# Filter.net
KiCad netlist of a schematic drawn in EAGLE
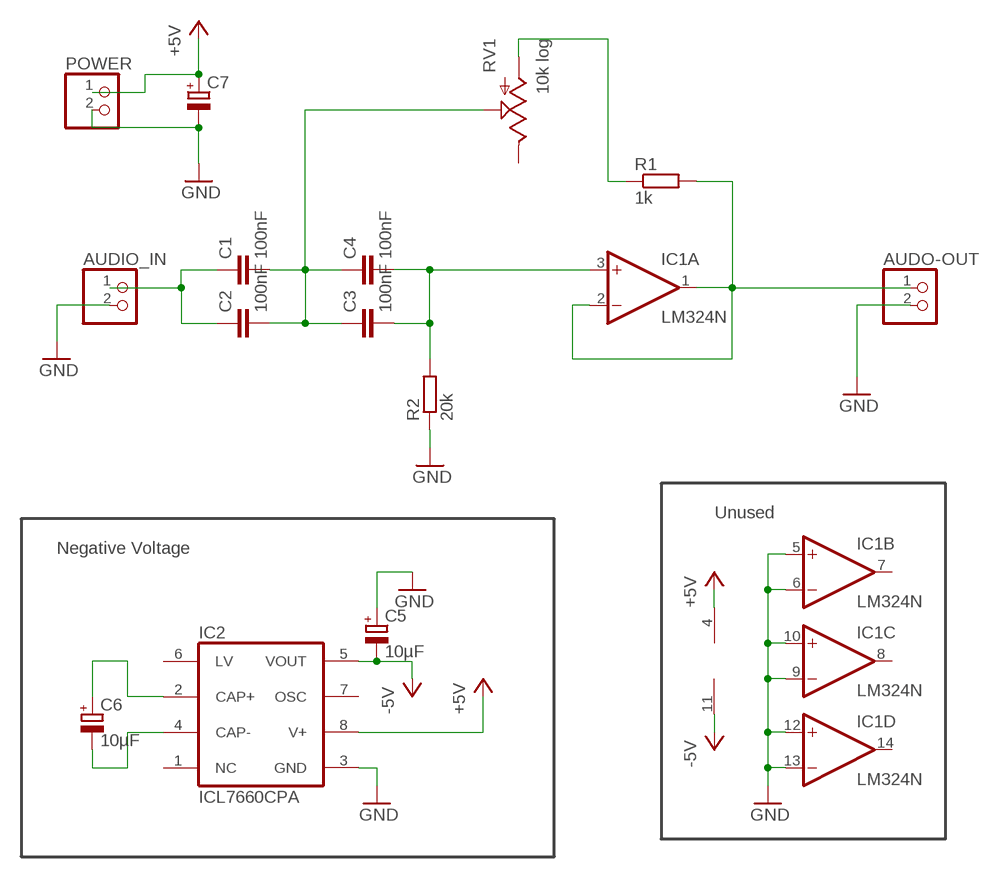
[diagram p0: schematic, sheet 1]

(export (version "E")
  (design (tool "Eeschema 10.0.6"))
  (components
    (comp (ref "AUDIO_IN")
      (value "PINHD-1X2")
      (footprint "eagle-import:1X02")
      (libsource (lib "eagle-import") (part "PINHD-1X2"))
    )
    (comp (ref "AUDO-OUT")
      (value "PINHD-1X2")
      (footprint "eagle-import:1X02")
      (libsource (lib "eagle-import") (part "PINHD-1X2"))
    )
    (comp (ref "C1")
      (value "100nF")
      (footprint "eagle-import:C025-025X050")
      (libsource (lib "eagle-import") (part "C-EU025-025X050"))
    )
    (comp (ref "C2")
      (value "100nF")
      (footprint "eagle-import:C025-025X050")
      (libsource (lib "eagle-import") (part "C-EU025-025X050"))
    )
    (comp (ref "C3")
      (value "100nF")
      (footprint "eagle-import:C025-025X050")
      (libsource (lib "eagle-import") (part "C-EU025-025X050"))
    )
    (comp (ref "C4")
      (value "100nF")
      (footprint "eagle-import:C025-025X050")
      (libsource (lib "eagle-import") (part "C-EU025-025X050"))
    )
    (comp (ref "C5")
      (value "10µF")
      (footprint "eagle-import:E2,5-6")
      (libsource (lib "eagle-import") (part "CPOL-EUE2.5-6"))
    )
    (comp (ref "C6")
      (value "10µF")
      (footprint "eagle-import:E2,5-6")
      (libsource (lib "eagle-import") (part "CPOL-EUE2.5-6"))
    )
    (comp (ref "C7")
      (value "CPOL-EUE2.5-6")
      (footprint "eagle-import:E2,5-6")
      (libsource (lib "eagle-import") (part "CPOL-EUE2.5-6"))
    )
    (comp (ref "IC1")
      (value "LM324N")
      (footprint "eagle-import:DIL14")
      (libsource (lib "eagle-import") (part "LM324N"))
    )
    (comp (ref "IC2")
      (value "ICL7660CPA")
      (footprint "eagle-import:DIL08")
      (fields (field (name "MF") "INTERSIL"))
      (libsource (lib "eagle-import") (part "ICL7660CPA"))
    )
    (comp (ref "POWER")
      (value "PINHD-1X2")
      (footprint "eagle-import:1X02")
      (libsource (lib "eagle-import") (part "PINHD-1X2"))
    )
    (comp (ref "R1")
      (value "1k")
      (footprint "eagle-import:0207_7")
      (libsource (lib "eagle-import") (part "R-EU_0207/7"))
    )
    (comp (ref "R2")
      (value "20k")
      (footprint "eagle-import:0207_7")
      (libsource (lib "eagle-import") (part "R-EU_0207/7"))
    )
    (comp (ref "RV1")
      (value "10k log")
      (footprint "eagle-import:ALPS_POT")
      (libsource (lib "eagle-import") (part "POT"))
    )
  )
  (nets
    (net (code "1") (name "+5V") (class "Default")
      (node (ref "C7") (pin "+") (pinfunction "+_+") (pintype "passive"))
      (node (ref "IC1") (pin "4") (pinfunction "V+_4") (pintype "power_in"))
      (node (ref "IC2") (pin "8") (pinfunction "V+_8") (pintype "power_in"))
      (node (ref "POWER") (pin "1") (pinfunction "1_1") (pintype "passive"))
    )
    (net (code "2") (name "-5V") (class "Default")
      (node (ref "C5") (pin "-") (pinfunction "-_-") (pintype "passive"))
      (node (ref "IC1") (pin "11") (pinfunction "V-_11") (pintype "power_in"))
      (node (ref "IC2") (pin "5") (pinfunction "VOUT_5") (pintype "output"))
    )
    (net (code "3") (name "GND") (class "Default")
      (node (ref "AUDIO_IN") (pin "2") (pinfunction "2_2") (pintype "passive"))
      (node (ref "AUDO-OUT") (pin "2") (pinfunction "2_2") (pintype "passive"))
      (node (ref "C5") (pin "+") (pinfunction "+_+") (pintype "passive"))
      (node (ref "C7") (pin "-") (pinfunction "-_-") (pintype "passive"))
      (node (ref "IC1") (pin "10") (pinfunction "+IN_10") (pintype "input"))
      (node (ref "IC1") (pin "12") (pinfunction "+IN_12") (pintype "input"))
      (node (ref "IC1") (pin "13") (pinfunction "-IN_13") (pintype "input"))
      (node (ref "IC1") (pin "5") (pinfunction "+IN_5") (pintype "input"))
      (node (ref "IC1") (pin "6") (pinfunction "-IN_6") (pintype "input"))
      (node (ref "IC1") (pin "9") (pinfunction "-IN_9") (pintype "input"))
      (node (ref "IC2") (pin "3") (pinfunction "GND_3") (pintype "power_in"))
      (node (ref "POWER") (pin "2") (pinfunction "2_2") (pintype "passive"))
      (node (ref "R2") (pin "1") (pinfunction "1_1") (pintype "passive"))
    )
    (net (code "4") (name "Net-(AUDIO_IN-Pad1)") (class "Default")
      (node (ref "AUDIO_IN") (pin "1") (pinfunction "1_1") (pintype "passive"))
      (node (ref "C1") (pin "1") (pinfunction "1_1") (pintype "passive"))
      (node (ref "C2") (pin "1") (pinfunction "1_1") (pintype "passive"))
    )
    (net (code "5") (name "Net-(IC1A-+IN)") (class "Default")
      (node (ref "C3") (pin "2") (pinfunction "2_2") (pintype "passive"))
      (node (ref "C4") (pin "2") (pinfunction "2_2") (pintype "passive"))
      (node (ref "IC1") (pin "3") (pinfunction "+IN_3") (pintype "input"))
      (node (ref "R2") (pin "2") (pinfunction "2_2") (pintype "passive"))
    )
    (net (code "6") (name "Net-(IC1A--IN)") (class "Default")
      (node (ref "AUDO-OUT") (pin "1") (pinfunction "1_1") (pintype "passive"))
      (node (ref "IC1") (pin "1") (pinfunction "OUT_1") (pintype "output"))
      (node (ref "IC1") (pin "2") (pinfunction "-IN_2") (pintype "input"))
      (node (ref "R1") (pin "2") (pinfunction "2_2") (pintype "passive"))
    )
    (net (code "7") (name "Net-(IC2-CAP+)") (class "Default")
      (node (ref "C6") (pin "+") (pinfunction "+_+") (pintype "passive"))
      (node (ref "IC2") (pin "2") (pinfunction "CAP+_2") (pintype "passive"))
    )
    (net (code "8") (name "Net-(IC2-CAP-)") (class "Default")
      (node (ref "C6") (pin "-") (pinfunction "-_-") (pintype "passive"))
      (node (ref "IC2") (pin "4") (pinfunction "CAP-_4") (pintype "passive"))
    )
    (net (code "9") (name "Net-(RV1-A)") (class "Default")
      (node (ref "R1") (pin "1") (pinfunction "1_1") (pintype "passive"))
      (node (ref "RV1") (pin "P$3") (pinfunction "A_P$3") (pintype "passive"))
    )
    (net (code "10") (name "Net-(RV1-S)") (class "Default")
      (node (ref "C1") (pin "2") (pinfunction "2_2") (pintype "passive"))
      (node (ref "C2") (pin "2") (pinfunction "2_2") (pintype "passive"))
      (node (ref "C3") (pin "1") (pinfunction "1_1") (pintype "passive"))
      (node (ref "C4") (pin "1") (pinfunction "1_1") (pintype "passive"))
      (node (ref "RV1") (pin "P$2") (pinfunction "S_P$2") (pintype "passive"))
    )
    (net (code "11") (name "unconnected-(IC1B-OUT-Pad7)") (class "Default")
      (node (ref "IC1") (pin "7") (pinfunction "OUT_7") (pintype "output"))
    )
    (net (code "12") (name "unconnected-(IC1C-OUT-Pad8)") (class "Default")
      (node (ref "IC1") (pin "8") (pinfunction "OUT_8") (pintype "output"))
    )
    (net (code "13") (name "unconnected-(IC1D-OUT-Pad14)") (class "Default")
      (node (ref "IC1") (pin "14") (pinfunction "OUT_14") (pintype "output"))
    )
    (net (code "14") (name "unconnected-(IC2-LV-Pad6)") (class "Default")
      (node (ref "IC2") (pin "6") (pinfunction "LV_6") (pintype "passive"))
    )
    (net (code "15") (name "unconnected-(IC2-NC-Pad1)") (class "Default")
      (node (ref "IC2") (pin "1") (pinfunction "NC_1") (pintype "no_connect"))
    )
    (net (code "16") (name "unconnected-(IC2-OSC-Pad7)") (class "Default")
      (node (ref "IC2") (pin "7") (pinfunction "OSC_7") (pintype "output"))
    )
    (net (code "17") (name "unconnected-(RV1-E-PadP$1)") (class "Default")
      (node (ref "RV1") (pin "P$1") (pinfunction "E_P$1") (pintype "passive"))
    )
  )
)
